# Sheet1.net
KiCad netlist of a schematic drawn in Altium Designer
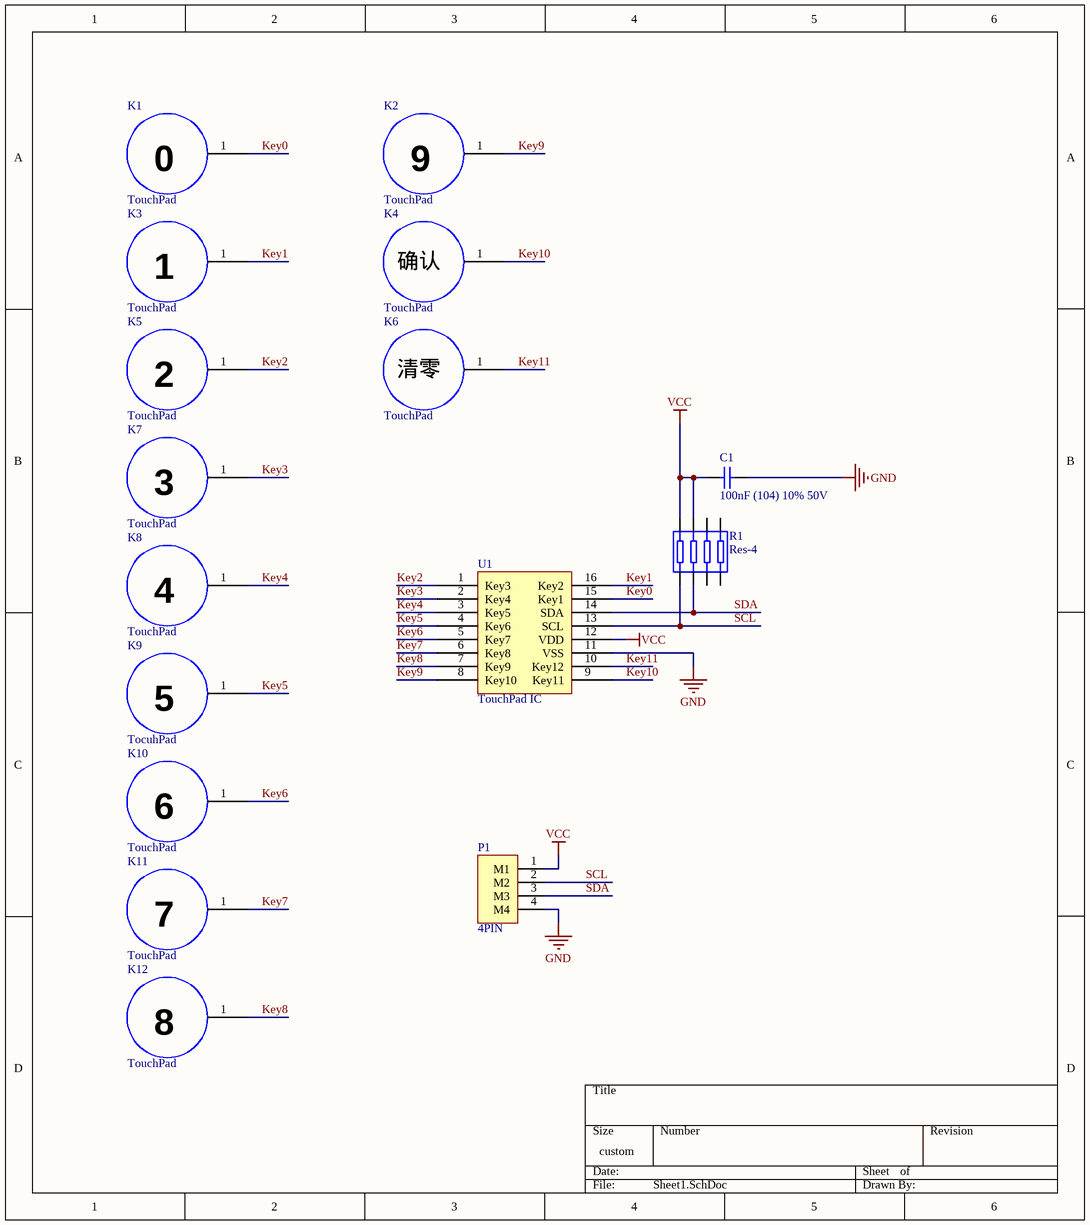
[diagram p0: Sheet1.SchDoc]

(export (version "E")
  (design (tool "Eeschema 10.0.6"))
  (components
    (comp (ref "C1")
      (value "100nF (104) 10% 50V")
      (footprint "0603_C")
      (description "贴片电容")
      (libsource (lib "Cap") (part "0603 100nF (104) 10% 50V"))
    )
    (comp (ref "K1") (value "TouchPad") (footprint "KEY0") (libsource (lib "Schlib3") (part "Key0")))
    (comp (ref "K2") (value "TouchPad") (footprint "KEY9") (libsource (lib "Schlib3") (part "Key9")))
    (comp (ref "K3") (value "TouchPad") (footprint "Key1") (libsource (lib "Schlib3") (part "Key1")))
    (comp (ref "K4") (value "TouchPad") (footprint "confirm") (libsource (lib "Schlib3") (part "confirm")))
    (comp (ref "K5") (value "TouchPad") (footprint "KEY2") (libsource (lib "Schlib3") (part "Key2")))
    (comp (ref "K6") (value "TouchPad") (footprint "concel") (libsource (lib "Schlib3") (part "cancel")))
    (comp (ref "K7") (value "TouchPad") (footprint "KEY3") (libsource (lib "Schlib3") (part "Key3")))
    (comp (ref "K8") (value "TouchPad") (footprint "KEY4") (libsource (lib "Schlib3") (part "key4")))
    (comp (ref "K9") (value "TocuhPad") (footprint "KEY5") (libsource (lib "Schlib3") (part "Key5")))
    (comp (ref "K10") (value "TouchPad") (footprint "KEY6") (libsource (lib "Schlib3") (part "Key6")))
    (comp (ref "K11") (value "TouchPad") (footprint "KEY7") (libsource (lib "Schlib3") (part "Key7")))
    (comp (ref "K12") (value "TouchPad") (footprint "KEY8") (libsource (lib "Schlib3") (part "Key8")))
    (comp (ref "P1") (value "4PIN") (footprint "PH2.0WS-4P") (libsource (lib "集大电协1.5") (part "接线端子-4PIN")))
    (comp (ref "R1")
      (value "Res-4")
      (footprint "res-4")
      (description "排阻")
      (libsource (lib "集大电协1.5") (part "Res-4"))
    )
    (comp (ref "U1")
      (value "TouchPad IC")
      (footprint "SOP127P600X175-16N")
      (libsource (lib "Schlib3") (part "BS8112A-3"))
    )
  )
  (nets
    (net (code "1") (name "/Key0") (class "Default")
      (node (ref "K1") (pin "1") (pinfunction "1_1") (pintype "passive"))
      (node (ref "U1") (pin "15") (pinfunction "Key1_15") (pintype "passive"))
    )
    (net (code "2") (name "/Key1") (class "Default")
      (node (ref "K3") (pin "1") (pinfunction "1_1") (pintype "passive"))
      (node (ref "U1") (pin "16") (pinfunction "Key2_16") (pintype "passive"))
    )
    (net (code "3") (name "/Key2") (class "Default")
      (node (ref "K5") (pin "1") (pinfunction "1_1") (pintype "passive"))
      (node (ref "U1") (pin "1") (pinfunction "Key3_1") (pintype "passive"))
    )
    (net (code "4") (name "/Key3") (class "Default")
      (node (ref "K7") (pin "1") (pinfunction "1_1") (pintype "passive"))
      (node (ref "U1") (pin "2") (pinfunction "Key4_2") (pintype "passive"))
    )
    (net (code "5") (name "/Key4") (class "Default")
      (node (ref "K8") (pin "1") (pinfunction "1_1") (pintype "passive"))
      (node (ref "U1") (pin "3") (pinfunction "Key5_3") (pintype "passive"))
    )
    (net (code "6") (name "/Key5") (class "Default")
      (node (ref "K9") (pin "1") (pinfunction "1_1") (pintype "passive"))
      (node (ref "U1") (pin "4") (pinfunction "Key6_4") (pintype "passive"))
    )
    (net (code "7") (name "/Key6") (class "Default")
      (node (ref "K10") (pin "1") (pinfunction "1_1") (pintype "passive"))
      (node (ref "U1") (pin "5") (pinfunction "Key7_5") (pintype "passive"))
    )
    (net (code "8") (name "/Key7") (class "Default")
      (node (ref "K11") (pin "1") (pinfunction "1_1") (pintype "passive"))
      (node (ref "U1") (pin "6") (pinfunction "Key8_6") (pintype "passive"))
    )
    (net (code "9") (name "/Key8") (class "Default")
      (node (ref "K12") (pin "1") (pinfunction "1_1") (pintype "passive"))
      (node (ref "U1") (pin "7") (pinfunction "Key9_7") (pintype "passive"))
    )
    (net (code "10") (name "/Key9") (class "Default")
      (node (ref "K2") (pin "1") (pinfunction "1_1") (pintype "passive"))
      (node (ref "U1") (pin "8") (pinfunction "Key10_8") (pintype "passive"))
    )
    (net (code "11") (name "/Key10") (class "Default")
      (node (ref "K4") (pin "1") (pinfunction "1_1") (pintype "passive"))
      (node (ref "U1") (pin "9") (pinfunction "Key11_9") (pintype "passive"))
    )
    (net (code "12") (name "/Key11") (class "Default")
      (node (ref "K6") (pin "1") (pinfunction "1_1") (pintype "passive"))
      (node (ref "U1") (pin "10") (pinfunction "Key12_10") (pintype "passive"))
    )
    (net (code "13") (name "/SCL") (class "Default")
      (node (ref "P1") (pin "2") (pinfunction "M2_2") (pintype "passive"))
      (node (ref "R1") (pin "5") (pinfunction "5_5") (pintype "passive"))
      (node (ref "U1") (pin "13") (pinfunction "SCL_13") (pintype "passive"))
    )
    (net (code "14") (name "/SDA") (class "Default")
      (node (ref "P1") (pin "3") (pinfunction "M3_3") (pintype "passive"))
      (node (ref "R1") (pin "6") (pinfunction "6_6") (pintype "passive"))
      (node (ref "U1") (pin "14") (pinfunction "SDA_14") (pintype "passive"))
    )
    (net (code "15") (name "GND") (class "Default")
      (node (ref "C1") (pin "2") (pinfunction "2_2") (pintype "passive"))
      (node (ref "P1") (pin "4") (pinfunction "M4_4") (pintype "passive"))
      (node (ref "U1") (pin "11") (pinfunction "VSS_11") (pintype "passive"))
    )
    (net (code "16") (name "VCC") (class "Default")
      (node (ref "C1") (pin "1") (pinfunction "1_1") (pintype "passive"))
      (node (ref "P1") (pin "1") (pinfunction "M1_1") (pintype "passive"))
      (node (ref "R1") (pin "3") (pinfunction "3_3") (pintype "passive"))
      (node (ref "R1") (pin "4") (pinfunction "4_4") (pintype "passive"))
      (node (ref "U1") (pin "12") (pinfunction "VDD_12") (pintype "passive"))
    )
    (net (code "17") (name "unconnected-(R1-Pad1)") (class "Default")
      (node (ref "R1") (pin "1") (pinfunction "1_1") (pintype "passive"))
    )
    (net (code "18") (name "unconnected-(R1-Pad2)") (class "Default")
      (node (ref "R1") (pin "2") (pinfunction "2_2") (pintype "passive"))
    )
    (net (code "19") (name "unconnected-(R1-Pad7)") (class "Default")
      (node (ref "R1") (pin "7") (pinfunction "7_7") (pintype "passive"))
    )
    (net (code "20") (name "unconnected-(R1-Pad8)") (class "Default")
      (node (ref "R1") (pin "8") (pinfunction "8_8") (pintype "passive"))
    )
  )
)
